# fuente1.net
KiCad netlist of a schematic drawn in Altium Designer
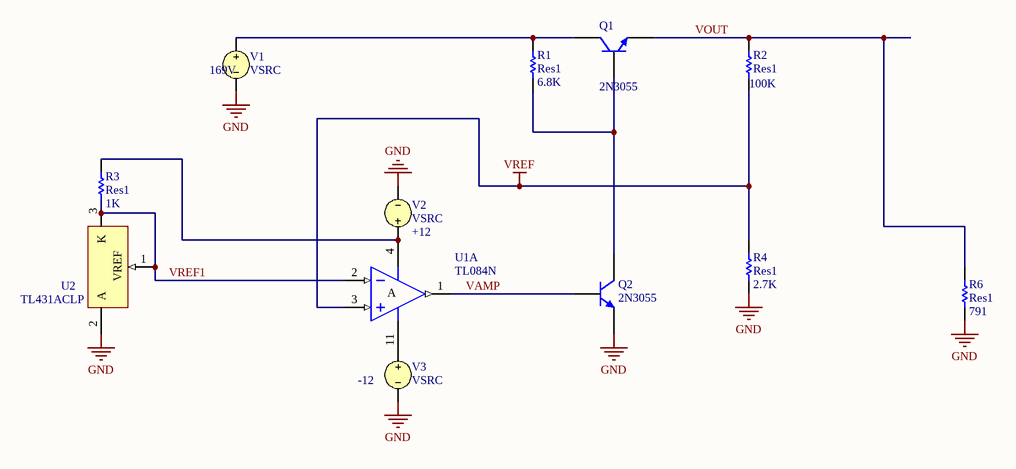
[diagram p0: fuente1.SchDoc]

(export (version "E")
  (design (tool "Eeschema 10.0.6"))
  (components
    (comp (ref "Q1")
      (value "2N3055")
      (footprint "TO-3")
      (description "Complementary Silicon Power Transistor")
      (fields (field (name "PUBLISHER") "Altium Limited"))
      (libsource (lib "ST Discrete BJT") (part "2N3055"))
    )
    (comp (ref "Q2")
      (value "2N3055")
      (footprint "TO-3")
      (description "Complementary Silicon Power Transistor")
      (fields (field (name "PUBLISHER") "Altium Limited"))
      (libsource (lib "ST Discrete BJT") (part "2N3055"))
    )
    (comp (ref "R1")
      (value "Res1")
      (footprint "AXIAL-0.3")
      (description "Resistor")
      (fields (field (name "ALTIUM_VALUE") "6.8K") (field (name "PUBLISHER") "Altium Limited"))
      (libsource (lib "Miscellaneous Devices") (part "Res1"))
    )
    (comp (ref "R2")
      (value "Res1")
      (footprint "AXIAL-0.3")
      (description "Resistor")
      (fields (field (name "ALTIUM_VALUE") "100K") (field (name "PUBLISHER") "Altium Limited"))
      (libsource (lib "Miscellaneous Devices") (part "Res1"))
    )
    (comp (ref "R3")
      (value "Res1")
      (footprint "AXIAL-0.3")
      (description "Resistor")
      (fields (field (name "ALTIUM_VALUE") "1K") (field (name "PUBLISHER") "Altium Limited"))
      (libsource (lib "Miscellaneous Devices") (part "Res1"))
    )
    (comp (ref "R4")
      (value "Res1")
      (footprint "AXIAL-0.3")
      (description "Resistor")
      (fields (field (name "ALTIUM_VALUE") "2.7K") (field (name "PUBLISHER") "Altium Limited"))
      (libsource (lib "Miscellaneous Devices") (part "Res1"))
    )
    (comp (ref "R6")
      (value "Res1")
      (footprint "AXIAL-0.3")
      (description "Resistor")
      (fields (field (name "ALTIUM_VALUE") "791") (field (name "PUBLISHER") "Altium Limited"))
      (libsource (lib "Miscellaneous Devices") (part "Res1"))
    )
    (comp (ref "U1")
      (value "TL084N")
      (footprint "N014")
      (description "JFET-Input Operational Amplifier")
      (fields (field (name "PUBLISHER") "Altium Limited"))
      (libsource (lib "TI Operational Amplifier") (part "TL084N"))
    )
    (comp (ref "U2")
      (value "TL431ACLP")
      (footprint "LP03")
      (description "Adjustable Precision Shunt Regulator")
      (fields (field (name "PUBLISHER") "Altium Limited"))
      (libsource (lib "TI Power Mgt Voltage Regulator") (part "TL431ACLP"))
    )
    (comp (ref "V1")
      (value "VSRC")
      (description "Voltage Source")
      (fields (field (name "ALTIUM_VALUE") "169V") (field (name "PUBLISHER") "Altium Limited"))
      (libsource (lib "Simulation Sources") (part "VSRC"))
    )
    (comp (ref "V2")
      (value "VSRC")
      (description "Voltage Source")
      (fields (field (name "ALTIUM_VALUE") "+12") (field (name "PUBLISHER") "Altium Limited"))
      (libsource (lib "Simulation Sources") (part "VSRC"))
    )
    (comp (ref "V3")
      (value "VSRC")
      (description "Voltage Source")
      (fields (field (name "ALTIUM_VALUE") "-12") (field (name "PUBLISHER") "Altium Limited"))
      (libsource (lib "Simulation Sources") (part "VSRC"))
    )
  )
  (nets
    (net (code "1") (name "/VAMP") (class "Default")
      (node (ref "Q2") (pin "1") (pinfunction "B_1") (pintype "passive"))
      (node (ref "U1") (pin "1") (pinfunction "OUT_1") (pintype "output"))
    )
    (net (code "2") (name "/VOUT") (class "Default")
      (node (ref "Q1") (pin "2") (pinfunction "E_2") (pintype "passive"))
      (node (ref "R2") (pin "2") (pinfunction "2_2") (pintype "passive"))
      (node (ref "R6") (pin "2") (pinfunction "2_2") (pintype "passive"))
    )
    (net (code "3") (name "/VREF1") (class "Default")
      (node (ref "R3") (pin "1") (pinfunction "1_1") (pintype "passive"))
      (node (ref "U1") (pin "2") (pinfunction "IN-_2") (pintype "input"))
      (node (ref "U2") (pin "1") (pinfunction "VREF_1") (pintype "input"))
      (node (ref "U2") (pin "3") (pinfunction "K_3") (pintype "power_in"))
    )
    (net (code "4") (name "GND") (class "Default")
      (node (ref "Q2") (pin "2") (pinfunction "E_2") (pintype "passive"))
      (node (ref "R4") (pin "1") (pinfunction "1_1") (pintype "passive"))
      (node (ref "R6") (pin "1") (pinfunction "1_1") (pintype "passive"))
      (node (ref "U2") (pin "2") (pinfunction "A_2") (pintype "power_in"))
      (node (ref "V1") (pin "2") (pinfunction "2_2") (pintype "passive"))
      (node (ref "V2") (pin "2") (pinfunction "2_2") (pintype "passive"))
      (node (ref "V3") (pin "2") (pinfunction "2_2") (pintype "passive"))
    )
    (net (code "5") (name "Net-(Q1-B)") (class "Default")
      (node (ref "Q1") (pin "1") (pinfunction "B_1") (pintype "passive"))
      (node (ref "Q2") (pin "3") (pinfunction "C_3") (pintype "passive"))
      (node (ref "R1") (pin "1") (pinfunction "1_1") (pintype "passive"))
    )
    (net (code "6") (name "Net-(Q1-C)") (class "Default")
      (node (ref "Q1") (pin "3") (pinfunction "C_3") (pintype "passive"))
      (node (ref "R1") (pin "2") (pinfunction "2_2") (pintype "passive"))
      (node (ref "V1") (pin "1") (pinfunction "1_1") (pintype "passive"))
    )
    (net (code "7") (name "Net-(U1A-V+)") (class "Default")
      (node (ref "R3") (pin "2") (pinfunction "2_2") (pintype "passive"))
      (node (ref "U1") (pin "4") (pinfunction "V+_4") (pintype "power_in"))
      (node (ref "V2") (pin "1") (pinfunction "1_1") (pintype "passive"))
    )
    (net (code "8") (name "Net-(U1A-V-)") (class "Default")
      (node (ref "U1") (pin "11") (pinfunction "V-_11") (pintype "power_in"))
      (node (ref "V3") (pin "1") (pinfunction "1_1") (pintype "passive"))
    )
    (net (code "9") (name "VREF") (class "Default")
      (node (ref "R2") (pin "1") (pinfunction "1_1") (pintype "passive"))
      (node (ref "R4") (pin "2") (pinfunction "2_2") (pintype "passive"))
      (node (ref "U1") (pin "3") (pinfunction "IN+_3") (pintype "input"))
    )
  )
)
